# Tead_Aliens_64A_CPU.net
KiCad netlist of a schematic drawn in Altium Designer
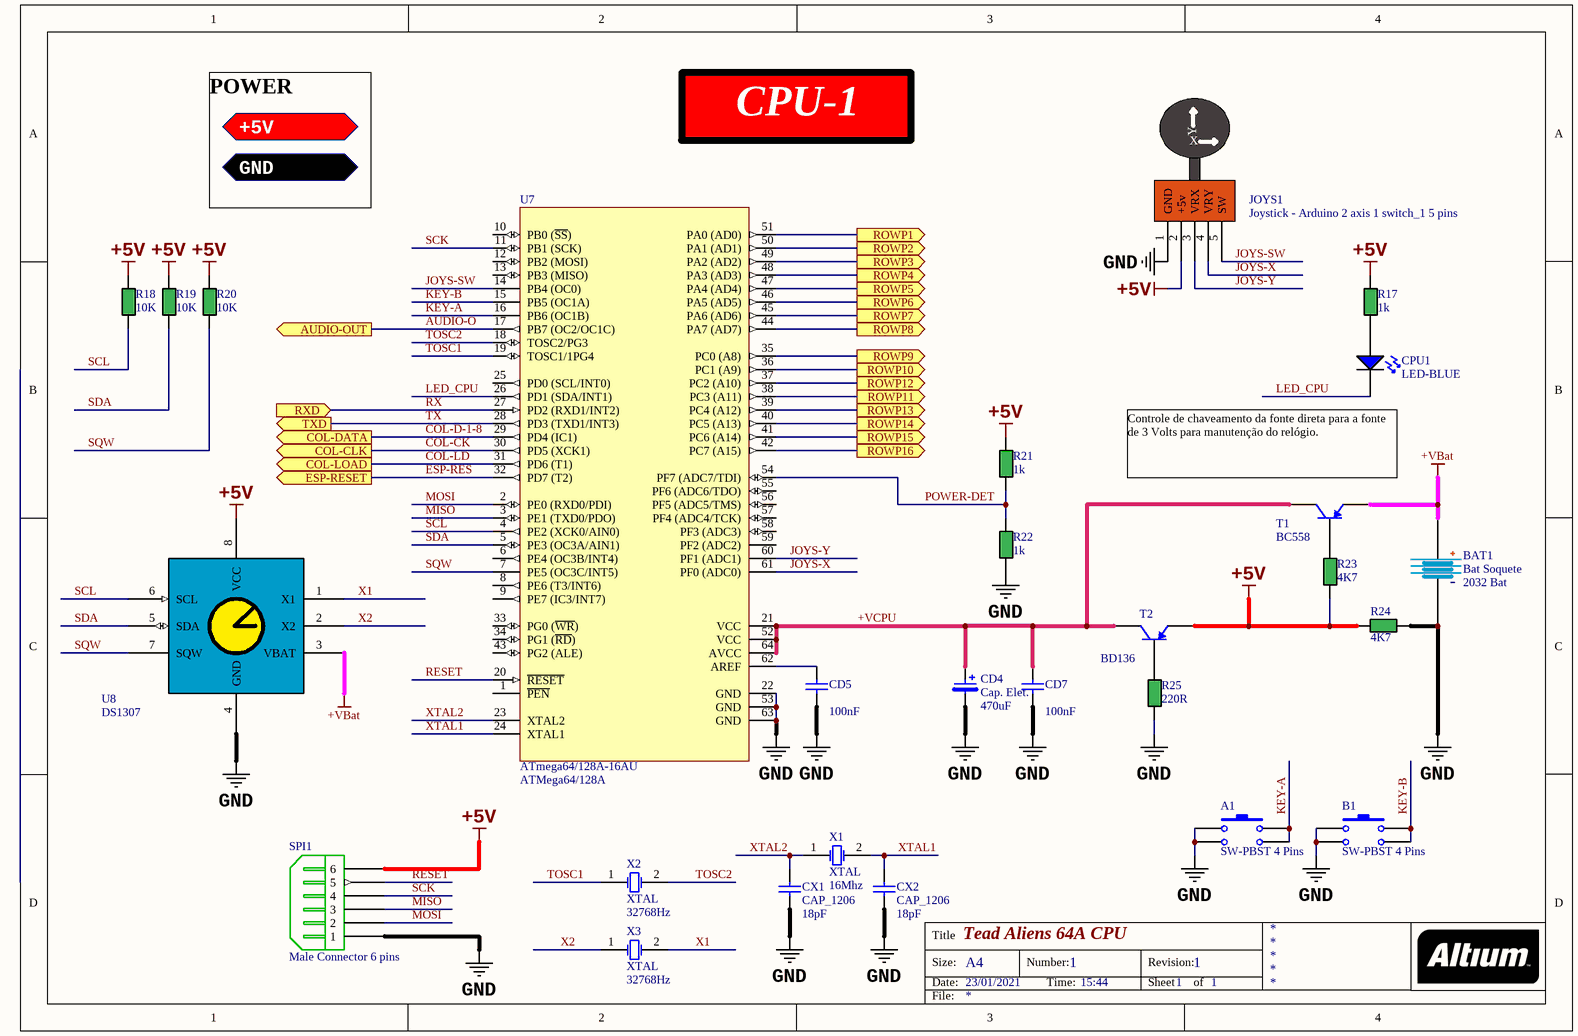
[diagram p0: Tead_Aliens_64A_CPU.SchDoc]

(export (version "E")
  (design (tool "Eeschema 10.0.6"))
  (components
    (comp (ref "A1")
      (value "SW-PBST 4 Pins")
      (footprint "SW-PBST 4 PINS - B3F")
      (fields (field (name "PUBLISHER") "Altium Limited"))
      (libsource (lib "NEPERMATH") (part "SW-PBST 4 Pins SKHH"))
    )
    (comp (ref "B1")
      (value "SW-PBST 4 Pins")
      (footprint "SW-PBST 4 PINS - B3F")
      (fields (field (name "PUBLISHER") "Altium Limited"))
      (libsource (lib "NEPERMATH") (part "SW-PBST 4 Pins SKHH"))
    )
    (comp (ref "BAT1")
      (value "Bat Soquete")
      (footprint "Batt Sup CR2025")
      (description "Bat 3.6V")
      (fields (field (name "ALTIUM_VALUE") "2032 Bat"))
      (libsource (lib "NEPERMATH") (part "Bat 3.6v"))
    )
    (comp (ref "CD4")
      (value "Cap. Elet.")
      (footprint "CAP ELE RAD 11mm H")
      (description "Capacitor Radial Eletrolitico")
      (fields (field (name "ALTIUM_VALUE") "470uF"))
      (libsource (lib "NEPERMATH") (part "CAP_RADIAL_ELETROLITICO"))
    )
    (comp (ref "CD5")
      (value "100nF")
      (footprint "CAP_1206")
      (description "SMD Capacitor 1206 size")
      (fields (field (name "Comment") "CAP_1206"))
      (libsource (lib "NEPERMATH") (part "CAP_1206"))
    )
    (comp (ref "CD7")
      (value "100nF")
      (footprint "CAP_1206")
      (description "SMD Capacitor 1206 size")
      (fields (field (name "Comment") "CAP_1206"))
      (libsource (lib "NEPERMATH") (part "CAP_1206"))
    )
    (comp (ref "CPU1")
      (value "LED-BLUE")
      (footprint "LED BLUE 3MM")
      (description "LED BLUE")
      (libsource (lib "NEPERMATH") (part "LED-BLUE"))
    )
    (comp (ref "CX1")
      (value "CAP_1206")
      (footprint "CAP_1206")
      (description "SMD Capacitor 1206 size")
      (fields (field (name "ALTIUM_VALUE") "18pF"))
      (libsource (lib "NEPERMATH") (part "CAP_1206"))
    )
    (comp (ref "CX2")
      (value "CAP_1206")
      (footprint "CAP_1206")
      (description "SMD Capacitor 1206 size")
      (fields (field (name "ALTIUM_VALUE") "18pF"))
      (libsource (lib "NEPERMATH") (part "CAP_1206"))
    )
    (comp (ref "JOYS1")
      (value "Joystick - Arduino 2 axis 1 switch_1 5 pins")
      (footprint "JOYSTICK ARDUINO 5 PINS 0 GRAUS")
      (description "Arduino Joystick 2 axis 1 switch 5 pins")
      (libsource (lib "NEPERMATH") (part "Joystick - Arduino 2 axis 1 switch_1 5 pins"))
    )
    (comp (ref "R17")
      (value "1k")
      (footprint "RES_0805")
      (description "Generic Resistor")
      (fields (field (name "Comment") "Resistor Generic"))
      (libsource (lib "NEPERMATH") (part "Resistor Generic"))
    )
    (comp (ref "R18")
      (value "10K")
      (footprint "RES_0805")
      (description "Generic Resistor")
      (fields (field (name "Comment") "Resistor Generic"))
      (libsource (lib "NEPERMATH") (part "Resistor Generic"))
    )
    (comp (ref "R19")
      (value "10K")
      (footprint "RES_0805")
      (description "Generic Resistor")
      (fields (field (name "Comment") "Resistor Generic"))
      (libsource (lib "NEPERMATH") (part "Resistor Generic"))
    )
    (comp (ref "R20")
      (value "10K")
      (footprint "RES_0805")
      (description "Generic Resistor")
      (fields (field (name "Comment") "Resistor Generic"))
      (libsource (lib "NEPERMATH") (part "Resistor Generic"))
    )
    (comp (ref "R21")
      (value "1k")
      (footprint "RES_0805")
      (description "Generic Resistor")
      (fields (field (name "Comment") "Resistor Generic"))
      (libsource (lib "NEPERMATH") (part "Resistor Generic"))
    )
    (comp (ref "R22")
      (value "1k")
      (footprint "RES_0805")
      (description "Generic Resistor")
      (fields (field (name "Comment") "Resistor Generic"))
      (libsource (lib "NEPERMATH") (part "Resistor Generic"))
    )
    (comp (ref "R23")
      (value "4K7")
      (footprint "RES_0805")
      (description "Generic Resistor")
      (fields (field (name "Comment") "Resistor Generic"))
      (libsource (lib "NEPERMATH") (part "Resistor Generic"))
    )
    (comp (ref "R24")
      (value "4K7")
      (footprint "RES_0805")
      (description "Generic Resistor")
      (fields (field (name "Comment") "Resistor Generic"))
      (libsource (lib "") (part "Resistor Generic_1"))
    )
    (comp (ref "R25")
      (value "220R")
      (footprint "RES 300 CR25")
      (description "Generic Resistor")
      (fields (field (name "Comment") "Resistor Generic"))
      (libsource (lib "NEPERMATH") (part "Resistor Generic"))
    )
    (comp (ref "SPI1")
      (value "Male Connector 6 pins")
      (footprint "BPSC-6")
      (libsource (lib "NEPERMATH") (part "Male Con 6 Pin"))
    )
    (comp (ref "T1")
      (value "BC558")
      (footprint "TO-92 - BIG")
      (description "General Bipolar Transistor NPN")
      (fields (field (name "Comment") "Transistor"))
      (libsource (lib "NEPERMATH") (part "T-PNP"))
    )
    (comp (ref "T2")
      (value "BD136")
      (footprint "TO126")
      (description "General Bipolar Transistor NPN")
      (fields (field (name "Comment") "Transistor"))
      (libsource (lib "NEPERMATH") (part "T-PNP"))
    )
    (comp (ref "U7")
      (value "ATmega64/128A-16AU")
      (footprint "64A_L")
      (description "8-Bit AVR Microcontroller with 128K Bytes of In-System Programmable Flash Memory")
      (fields (field (name "ALTIUM_VALUE") "ATMega64/128A") (field (name "PUBLISHER") "Altium Limited"))
      (libsource (lib "NEPERMATH") (part "ATmega128A-16AU"))
    )
    (comp (ref "U8")
      (value "DS1307")
      (footprint "DIP8")
      (description "Real Time Clock")
      (libsource (lib "NEPERMATH") (part "RTC"))
    )
    (comp (ref "X1")
      (value "XTAL")
      (footprint "XTAL HC49-4H")
      (description "Crystal Oscillator")
      (fields (field (name "ALTIUM_VALUE") "16Mhz"))
      (libsource (lib "NEPERMATH") (part "XTAL"))
    )
    (comp (ref "X2")
      (value "XTAL")
      (footprint "XTAL CILINDRIC DEITADO")
      (description "Crystal Oscillator")
      (fields (field (name "ALTIUM_VALUE") "32768Hz"))
      (libsource (lib "NEPERMATH") (part "XTAL"))
    )
    (comp (ref "X3")
      (value "XTAL")
      (footprint "XTAL CILINDRIC DEITADO")
      (description "Crystal Oscillator")
      (fields (field (name "ALTIUM_VALUE") "32768Hz"))
      (libsource (lib "NEPERMATH") (part "XTAL"))
    )
  )
  (nets
    (net (code "1") (name "+5V") (class "Default")
      (node (ref "JOYS1") (pin "2") (pinfunction "+5v_2") (pintype "power_in"))
      (node (ref "R17") (pin "2") (pinfunction "2_2") (pintype "passive"))
      (node (ref "R18") (pin "2") (pinfunction "2_2") (pintype "passive"))
      (node (ref "R19") (pin "2") (pinfunction "2_2") (pintype "passive"))
      (node (ref "R20") (pin "2") (pinfunction "2_2") (pintype "passive"))
      (node (ref "R21") (pin "2") (pinfunction "2_2") (pintype "passive"))
      (node (ref "R23") (pin "1") (pinfunction "1_1") (pintype "passive"))
      (node (ref "R24") (pin "2") (pinfunction "2_2") (pintype "passive"))
      (node (ref "SPI1") (pin "6") (pinfunction "6_6") (pintype "passive"))
      (node (ref "T2") (pin "1") (pinfunction "E_1") (pintype "passive"))
      (node (ref "U8") (pin "8") (pinfunction "VCC_8") (pintype "power_in"))
    )
    (net (code "2") (name "+VBat") (class "Default")
      (node (ref "BAT1") (pin "1") (pinfunction "1_1") (pintype "passive"))
      (node (ref "T1") (pin "1") (pinfunction "E_1") (pintype "passive"))
      (node (ref "U8") (pin "3") (pinfunction "VBAT_3") (pintype "power_in"))
    )
    (net (code "3") (name "/+VCPU") (class "Default")
      (node (ref "CD4") (pin "1") (pinfunction "1_1") (pintype "passive"))
      (node (ref "CD7") (pin "2") (pinfunction "2_2") (pintype "passive"))
      (node (ref "T1") (pin "3") (pinfunction "C_3") (pintype "passive"))
      (node (ref "T2") (pin "3") (pinfunction "C_3") (pintype "passive"))
      (node (ref "U7") (pin "21") (pinfunction "VCC_21") (pintype "power_in"))
      (node (ref "U7") (pin "52") (pinfunction "VCC_52") (pintype "power_in"))
      (node (ref "U7") (pin "64") (pinfunction "AVCC_64") (pintype "power_in"))
    )
    (net (code "4") (name "/AUDIO-O") (class "Default")
      (node (ref "U7") (pin "17") (pinfunction "PB7_(OC2/OC1C)_17") (pintype "output"))
    )
    (net (code "5") (name "/COL-CK") (class "Default")
      (node (ref "U7") (pin "30") (pinfunction "PD5_(XCK1)_30") (pintype "output"))
    )
    (net (code "6") (name "/COL-D-1-8") (class "Default")
      (node (ref "U7") (pin "29") (pinfunction "PD4_(IC1)_29") (pintype "output"))
    )
    (net (code "7") (name "/COL-LD") (class "Default")
      (node (ref "U7") (pin "31") (pinfunction "PD6_(T1)_31") (pintype "output"))
    )
    (net (code "8") (name "/ESP-RES") (class "Default")
      (node (ref "U7") (pin "32") (pinfunction "PD7_(T2)_32") (pintype "output"))
    )
    (net (code "9") (name "/JOYS-SW") (class "Default")
      (node (ref "JOYS1") (pin "5") (pinfunction "SW_5") (pintype "power_in"))
      (node (ref "U7") (pin "14") (pinfunction "PB4_(OC0)_14") (pintype "passive"))
    )
    (net (code "10") (name "/JOYS-X") (class "Default")
      (node (ref "JOYS1") (pin "4") (pinfunction "VRY_4") (pintype "power_in"))
      (node (ref "U7") (pin "61") (pinfunction "PF0_(ADC0)_61") (pintype "passive"))
    )
    (net (code "11") (name "/JOYS-Y") (class "Default")
      (node (ref "JOYS1") (pin "3") (pinfunction "VRX_3") (pintype "passive"))
      (node (ref "U7") (pin "60") (pinfunction "PF1_(ADC1)_60") (pintype "passive"))
    )
    (net (code "12") (name "/KEY-A") (class "Default")
      (node (ref "A1") (pin "3") (pinfunction "3_3") (pintype "passive"))
      (node (ref "A1") (pin "4") (pinfunction "4_4") (pintype "passive"))
      (node (ref "U7") (pin "16") (pinfunction "PB6_(OC1B)_16") (pintype "passive"))
    )
    (net (code "13") (name "/KEY-B") (class "Default")
      (node (ref "B1") (pin "3") (pinfunction "3_3") (pintype "passive"))
      (node (ref "B1") (pin "4") (pinfunction "4_4") (pintype "passive"))
      (node (ref "U7") (pin "15") (pinfunction "PB5_(OC1A)_15") (pintype "passive"))
    )
    (net (code "14") (name "/LED_CPU") (class "Default")
      (node (ref "CPU1") (pin "K") (pinfunction "K_K") (pintype "passive"))
      (node (ref "U7") (pin "26") (pinfunction "PD1_(SDA/INT1)_26") (pintype "output"))
    )
    (net (code "15") (name "/MISO") (class "Default")
      (node (ref "SPI1") (pin "3") (pinfunction "3_3") (pintype "passive"))
      (node (ref "U7") (pin "3") (pinfunction "PE1_(TXD0/PDO)_3") (pintype "bidirectional"))
    )
    (net (code "16") (name "/MOSI") (class "Default")
      (node (ref "SPI1") (pin "2") (pinfunction "2_2") (pintype "passive"))
      (node (ref "U7") (pin "2") (pinfunction "PE0_(RXD0/PDI)_2") (pintype "bidirectional"))
    )
    (net (code "17") (name "/POWER-DET") (class "Default")
      (node (ref "R21") (pin "1") (pinfunction "1_1") (pintype "passive"))
      (node (ref "R22") (pin "2") (pinfunction "2_2") (pintype "passive"))
      (node (ref "U7") (pin "54") (pinfunction "PF7_(ADC7/TDI)_54") (pintype "bidirectional"))
    )
    (net (code "18") (name "/RESET") (class "Default")
      (node (ref "SPI1") (pin "5") (pinfunction "5_5") (pintype "output"))
      (node (ref "U7") (pin "20") (pinfunction "~{RESET}_20") (pintype "input"))
    )
    (net (code "19") (name "/ROWP1") (class "Default")
      (node (ref "U7") (pin "51") (pinfunction "PA0_(AD0)_51") (pintype "output"))
    )
    (net (code "20") (name "/ROWP2") (class "Default")
      (node (ref "U7") (pin "50") (pinfunction "PA1_(AD1)_50") (pintype "output"))
    )
    (net (code "21") (name "/ROWP3") (class "Default")
      (node (ref "U7") (pin "49") (pinfunction "PA2_(AD2)_49") (pintype "output"))
    )
    (net (code "22") (name "/ROWP4") (class "Default")
      (node (ref "U7") (pin "48") (pinfunction "PA3_(AD3)_48") (pintype "output"))
    )
    (net (code "23") (name "/ROWP5") (class "Default")
      (node (ref "U7") (pin "47") (pinfunction "PA4_(AD4)_47") (pintype "output"))
    )
    (net (code "24") (name "/ROWP6") (class "Default")
      (node (ref "U7") (pin "46") (pinfunction "PA5_(AD5)_46") (pintype "output"))
    )
    (net (code "25") (name "/ROWP7") (class "Default")
      (node (ref "U7") (pin "45") (pinfunction "PA6_(AD6)_45") (pintype "output"))
    )
    (net (code "26") (name "/ROWP8") (class "Default")
      (node (ref "U7") (pin "44") (pinfunction "PA7_(AD7)_44") (pintype "output"))
    )
    (net (code "27") (name "/ROWP9") (class "Default")
      (node (ref "U7") (pin "35") (pinfunction "PC0_(A8)_35") (pintype "output"))
    )
    (net (code "28") (name "/ROWP10") (class "Default")
      (node (ref "U7") (pin "36") (pinfunction "PC1_(A9)_36") (pintype "output"))
    )
    (net (code "29") (name "/ROWP11") (class "Default")
      (node (ref "U7") (pin "38") (pinfunction "PC3_(A11)_38") (pintype "output"))
    )
    (net (code "30") (name "/ROWP12") (class "Default")
      (node (ref "U7") (pin "37") (pinfunction "PC2_(A10)_37") (pintype "output"))
    )
    (net (code "31") (name "/ROWP13") (class "Default")
      (node (ref "U7") (pin "39") (pinfunction "PC4_(A12)_39") (pintype "output"))
    )
    (net (code "32") (name "/ROWP14") (class "Default")
      (node (ref "U7") (pin "40") (pinfunction "PC5_(A13)_40") (pintype "output"))
    )
    (net (code "33") (name "/ROWP15") (class "Default")
      (node (ref "U7") (pin "41") (pinfunction "PC6_(A14)_41") (pintype "output"))
    )
    (net (code "34") (name "/ROWP16") (class "Default")
      (node (ref "U7") (pin "42") (pinfunction "PC7_(A15)_42") (pintype "output"))
    )
    (net (code "35") (name "/RX") (class "Default")
      (node (ref "U7") (pin "27") (pinfunction "PD2_(RXD1/INT2)_27") (pintype "input"))
    )
    (net (code "36") (name "/SCK") (class "Default")
      (node (ref "SPI1") (pin "4") (pinfunction "4_4") (pintype "passive"))
      (node (ref "U7") (pin "11") (pinfunction "PB1_(SCK)_11") (pintype "bidirectional"))
    )
    (net (code "37") (name "/SCL") (class "Default")
      (node (ref "R18") (pin "1") (pinfunction "1_1") (pintype "passive"))
      (node (ref "U7") (pin "4") (pinfunction "PE2_(XCK0/AIN0)_4") (pintype "output"))
      (node (ref "U8") (pin "6") (pinfunction "SCL_6") (pintype "input"))
    )
    (net (code "38") (name "/SDA") (class "Default")
      (node (ref "R19") (pin "1") (pinfunction "1_1") (pintype "passive"))
      (node (ref "U7") (pin "5") (pinfunction "PE3_(OC3A/AIN1)_5") (pintype "bidirectional"))
      (node (ref "U8") (pin "5") (pinfunction "SDA_5") (pintype "bidirectional"))
    )
    (net (code "39") (name "/SQW") (class "Default")
      (node (ref "R20") (pin "1") (pinfunction "1_1") (pintype "passive"))
      (node (ref "U7") (pin "7") (pinfunction "PE5_(OC3C/INT5)_7") (pintype "passive"))
      (node (ref "U8") (pin "7") (pinfunction "SQW_7") (pintype "open_collector"))
    )
    (net (code "40") (name "/TOSC1") (class "Default")
      (node (ref "U7") (pin "19") (pinfunction "TOSC1/1PG4_19") (pintype "bidirectional"))
      (node (ref "X2") (pin "1") (pinfunction "OSC1_1") (pintype "passive"))
    )
    (net (code "41") (name "/TOSC2") (class "Default")
      (node (ref "U7") (pin "18") (pinfunction "TOSC2/PG3_18") (pintype "bidirectional"))
      (node (ref "X2") (pin "2") (pinfunction "OSC2_2") (pintype "passive"))
    )
    (net (code "42") (name "/TX") (class "Default")
      (node (ref "U7") (pin "28") (pinfunction "PD3_(TXD1/INT3)_28") (pintype "output"))
    )
    (net (code "43") (name "/X1") (class "Default")
      (node (ref "U8") (pin "1") (pinfunction "X1_1") (pintype "passive"))
      (node (ref "X3") (pin "2") (pinfunction "OSC2_2") (pintype "passive"))
    )
    (net (code "44") (name "/X2") (class "Default")
      (node (ref "U8") (pin "2") (pinfunction "X2_2") (pintype "passive"))
      (node (ref "X3") (pin "1") (pinfunction "OSC1_1") (pintype "passive"))
    )
    (net (code "45") (name "/XTAL1") (class "Default")
      (node (ref "CX2") (pin "2") (pinfunction "2_2") (pintype "passive"))
      (node (ref "U7") (pin "24") (pinfunction "XTAL1_24") (pintype "passive"))
      (node (ref "X1") (pin "2") (pinfunction "OSC2_2") (pintype "passive"))
    )
    (net (code "46") (name "/XTAL2") (class "Default")
      (node (ref "CX1") (pin "2") (pinfunction "2_2") (pintype "passive"))
      (node (ref "U7") (pin "23") (pinfunction "XTAL2_23") (pintype "passive"))
      (node (ref "X1") (pin "1") (pinfunction "OSC1_1") (pintype "passive"))
    )
    (net (code "47") (name "GND") (class "Default")
      (node (ref "A1") (pin "1") (pinfunction "1_1") (pintype "passive"))
      (node (ref "A1") (pin "2") (pinfunction "2_2") (pintype "passive"))
      (node (ref "B1") (pin "1") (pinfunction "1_1") (pintype "passive"))
      (node (ref "B1") (pin "2") (pinfunction "2_2") (pintype "passive"))
      (node (ref "BAT1") (pin "2") (pinfunction "2_2") (pintype "passive"))
      (node (ref "CD4") (pin "2") (pinfunction "2_2") (pintype "passive"))
      (node (ref "CD5") (pin "1") (pinfunction "1_1") (pintype "passive"))
      (node (ref "CD7") (pin "1") (pinfunction "1_1") (pintype "passive"))
      (node (ref "CX1") (pin "1") (pinfunction "1_1") (pintype "passive"))
      (node (ref "CX2") (pin "1") (pinfunction "1_1") (pintype "passive"))
      (node (ref "JOYS1") (pin "1") (pinfunction "GND_1") (pintype "power_in"))
      (node (ref "R22") (pin "1") (pinfunction "1_1") (pintype "passive"))
      (node (ref "R24") (pin "1") (pinfunction "1_1") (pintype "passive"))
      (node (ref "R25") (pin "1") (pinfunction "1_1") (pintype "passive"))
      (node (ref "SPI1") (pin "1") (pinfunction "1_1") (pintype "passive"))
      (node (ref "U7") (pin "22") (pinfunction "GND_22") (pintype "power_in"))
      (node (ref "U7") (pin "53") (pinfunction "GND_53") (pintype "power_in"))
      (node (ref "U7") (pin "63") (pinfunction "GND_63") (pintype "power_in"))
      (node (ref "U8") (pin "4") (pinfunction "GND_4") (pintype "power_in"))
    )
    (net (code "48") (name "Net-(CPU1-PadA)") (class "Default")
      (node (ref "CPU1") (pin "A") (pinfunction "A_A") (pintype "passive"))
      (node (ref "R17") (pin "1") (pinfunction "1_1") (pintype "passive"))
    )
    (net (code "49") (name "Net-(T1-B)") (class "Default")
      (node (ref "R23") (pin "2") (pinfunction "2_2") (pintype "passive"))
      (node (ref "T1") (pin "2") (pinfunction "B_2") (pintype "passive"))
    )
    (net (code "50") (name "Net-(T2-B)") (class "Default")
      (node (ref "R25") (pin "2") (pinfunction "2_2") (pintype "passive"))
      (node (ref "T2") (pin "2") (pinfunction "B_2") (pintype "passive"))
    )
    (net (code "51") (name "Net-(U7-AREF)") (class "Default")
      (node (ref "CD5") (pin "2") (pinfunction "2_2") (pintype "passive"))
      (node (ref "U7") (pin "62") (pinfunction "AREF_62") (pintype "passive"))
    )
    (net (code "52") (name "unconnected-(U7-PB0_(~{SS})-Pad10)") (class "Default")
      (node (ref "U7") (pin "10") (pinfunction "PB0_(~{SS})_10") (pintype "bidirectional"))
    )
    (net (code "53") (name "unconnected-(U7-PB2_(MOSI)-Pad12)") (class "Default")
      (node (ref "U7") (pin "12") (pinfunction "PB2_(MOSI)_12") (pintype "bidirectional"))
    )
    (net (code "54") (name "unconnected-(U7-PB3_(MISO)-Pad13)") (class "Default")
      (node (ref "U7") (pin "13") (pinfunction "PB3_(MISO)_13") (pintype "bidirectional"))
    )
    (net (code "55") (name "unconnected-(U7-PD0_(SCL{slash}INT0)-Pad25)") (class "Default")
      (node (ref "U7") (pin "25") (pinfunction "PD0_(SCL/INT0)_25") (pintype "output"))
    )
    (net (code "56") (name "unconnected-(U7-PE4_(OC3B{slash}INT4)-Pad6)") (class "Default")
      (node (ref "U7") (pin "6") (pinfunction "PE4_(OC3B/INT4)_6") (pintype "output"))
    )
    (net (code "57") (name "unconnected-(U7-PE6_(T3{slash}INT6)-Pad8)") (class "Default")
      (node (ref "U7") (pin "8") (pinfunction "PE6_(T3/INT6)_8") (pintype "output"))
    )
    (net (code "58") (name "unconnected-(U7-PE7_(IC3{slash}INT7)-Pad9)") (class "Default")
      (node (ref "U7") (pin "9") (pinfunction "PE7_(IC3/INT7)_9") (pintype "output"))
    )
    (net (code "59") (name "unconnected-(U7-PF2_(ADC2)-Pad59)") (class "Default")
      (node (ref "U7") (pin "59") (pinfunction "PF2_(ADC2)_59") (pintype "passive"))
    )
    (net (code "60") (name "unconnected-(U7-PF3_(ADC3)-Pad58)") (class "Default")
      (node (ref "U7") (pin "58") (pinfunction "PF3_(ADC3)_58") (pintype "bidirectional"))
    )
    (net (code "61") (name "unconnected-(U7-PF4_(ADC4{slash}TCK)-Pad57)") (class "Default")
      (node (ref "U7") (pin "57") (pinfunction "PF4_(ADC4/TCK)_57") (pintype "bidirectional"))
    )
    (net (code "62") (name "unconnected-(U7-PF5_(ADC5{slash}TMS)-Pad56)") (class "Default")
      (node (ref "U7") (pin "56") (pinfunction "PF5_(ADC5/TMS)_56") (pintype "bidirectional"))
    )
    (net (code "63") (name "unconnected-(U7-PF6_(ADC6{slash}TDO)-Pad55)") (class "Default")
      (node (ref "U7") (pin "55") (pinfunction "PF6_(ADC6/TDO)_55") (pintype "bidirectional"))
    )
    (net (code "64") (name "unconnected-(U7-PG0_(~{WR})-Pad33)") (class "Default")
      (node (ref "U7") (pin "33") (pinfunction "PG0_(~{WR})_33") (pintype "bidirectional"))
    )
    (net (code "65") (name "unconnected-(U7-PG1_(~{RD})-Pad34)") (class "Default")
      (node (ref "U7") (pin "34") (pinfunction "PG1_(~{RD})_34") (pintype "bidirectional"))
    )
    (net (code "66") (name "unconnected-(U7-PG2_(ALE)-Pad43)") (class "Default")
      (node (ref "U7") (pin "43") (pinfunction "PG2_(ALE)_43") (pintype "bidirectional"))
    )
    (net (code "67") (name "unconnected-(U7-~{PEN}-Pad1)") (class "Default")
      (node (ref "U7") (pin "1") (pinfunction "~{PEN}_1") (pintype "passive"))
    )
  )
)
